# Farm_Pump.net
KiCad netlist of a schematic drawn in Altium Designer
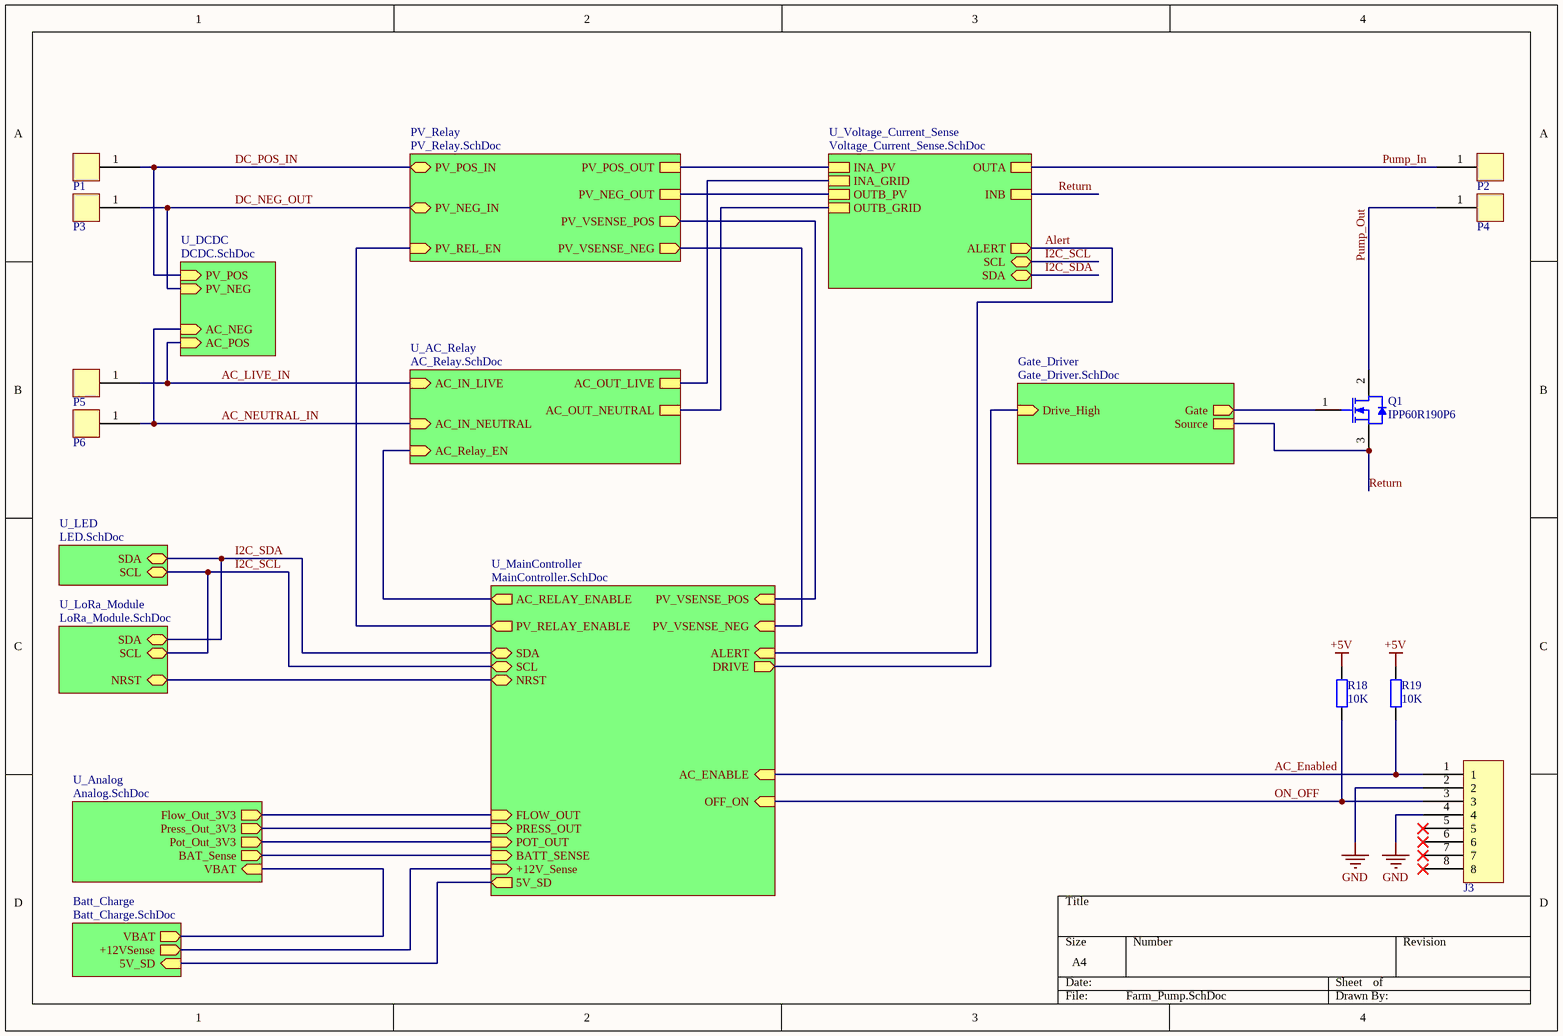
[diagram p0: Farm_Pump.SchDoc]

(export (version "E")
  (design (tool "Eeschema 10.0.6"))
  (components
    (comp (ref "J3")
      (value "MTJ-885X1")
      (footprint "MTJ-885X1")
      (fields (field (name "MANUFACTURER") "MODULAR JACK RJ45 8P8C"))
      (libsource (lib "Database_library") (part "MTJ-885X1"))
    )
    (comp (ref "P1")
      (value "1719189")
      (footprint "1719189")
      (fields (field (name "VOLTAGE") "1000") (field (name "MANUFACTURER") "Phoenix Contact"))
      (libsource (lib "Database_library") (part "1719189"))
    )
    (comp (ref "P2")
      (value "1719189")
      (footprint "1719189")
      (fields (field (name "VOLTAGE") "1000") (field (name "MANUFACTURER") "Phoenix Contact"))
      (libsource (lib "") (part "1719189_1"))
    )
    (comp (ref "P3")
      (value "1719189")
      (footprint "1719189")
      (fields (field (name "VOLTAGE") "1000") (field (name "MANUFACTURER") "Phoenix Contact"))
      (libsource (lib "Database_library") (part "1719189"))
    )
    (comp (ref "P4")
      (value "1719189")
      (footprint "1719189")
      (fields (field (name "VOLTAGE") "1000") (field (name "MANUFACTURER") "Phoenix Contact"))
      (libsource (lib "") (part "1719189_1"))
    )
    (comp (ref "P5")
      (value "1719189")
      (footprint "1719189")
      (fields (field (name "VOLTAGE") "1000") (field (name "MANUFACTURER") "Phoenix Contact"))
      (libsource (lib "Database_library") (part "1719189"))
    )
    (comp (ref "P6")
      (value "1719189")
      (footprint "1719189")
      (fields (field (name "VOLTAGE") "1000") (field (name "MANUFACTURER") "Phoenix Contact"))
      (libsource (lib "Database_library") (part "1719189"))
    )
    (comp (ref "Q1")
      (value "IPP60R190P6")
      (footprint "INF-PG-TO220-3-1_A_V")
      (description "N-Channel CoolMOS(TM) P6 Power Transistor, 600 V VDS, -55 to 150 degC, PG-TO220-3, Tube, Green")
      (fields (field (name "MANUFACTURER") "Infineon"))
      (libsource (lib "Altium Content Vault") (part "INF-NEMOS-GDS-3"))
    )
    (comp (ref "R18")
      (value "10K")
      (footprint "RES 0603/1608")
      (description "RES SMD 10K OHM 0.1% 1/10W 0603")
      (fields (field (name "PART NUMBER") "RG1608P-103-B-T5") (field (name "TOLERANCE") "0.1%"))
      (libsource (lib "electric_racing_lib") (part "Resistor"))
    )
    (comp (ref "R19")
      (value "10K")
      (footprint "RES 0603/1608")
      (description "RES SMD 10K OHM 0.1% 1/10W 0603")
      (fields (field (name "PART NUMBER") "RG1608P-103-B-T5") (field (name "TOLERANCE") "0.1%"))
      (libsource (lib "electric_racing_lib") (part "Resistor"))
    )
  )
  (nets
    (net (code "1") (name "+5V") (class "Default")
      (node (ref "R18") (pin "2") (pinfunction "2_2") (pintype "passive"))
      (node (ref "R19") (pin "2") (pinfunction "2_2") (pintype "passive"))
    )
    (net (code "4") (name "/AC_Enabled") (class "Default")
      (node (ref "J3") (pin "1") (pinfunction "1_1") (pintype "passive"))
      (node (ref "R19") (pin "1") (pinfunction "1_1") (pintype "passive"))
    )
    (net (code "5") (name "/AC_LIVE_IN") (class "Default")
      (node (ref "P5") (pin "1") (pinfunction "1_1") (pintype "passive"))
    )
    (net (code "6") (name "/AC_NEUTRAL_IN") (class "Default")
      (node (ref "P6") (pin "1") (pinfunction "1_1") (pintype "passive"))
    )
    (net (code "12") (name "/DC_NEG_OUT") (class "Default")
      (node (ref "P3") (pin "1") (pinfunction "1_1") (pintype "passive"))
    )
    (net (code "13") (name "/DC_POS_IN") (class "Default")
      (node (ref "P1") (pin "1") (pinfunction "1_1") (pintype "passive"))
    )
    (net (code "16") (name "/Gate") (class "Default")
      (node (ref "Q1") (pin "1") (pinfunction "GATE_1") (pintype "passive"))
    )
    (net (code "21") (name "/ON_OFF") (class "Default")
      (node (ref "J3") (pin "3") (pinfunction "3_3") (pintype "passive"))
      (node (ref "R18") (pin "1") (pinfunction "1_1") (pintype "passive"))
    )
    (net (code "28") (name "/Pump_In") (class "Default")
      (node (ref "P2") (pin "1") (pinfunction "1_1") (pintype "passive"))
    )
    (net (code "29") (name "/Pump_Out") (class "Default")
      (node (ref "P4") (pin "1") (pinfunction "1_1") (pintype "passive"))
      (node (ref "Q1") (pin "2") (pinfunction "DRAIN_2") (pintype "passive"))
    )
    (net (code "30") (name "/Return") (class "Default")
      (node (ref "Q1") (pin "3") (pinfunction "SOURCE_3") (pintype "passive"))
    )
    (net (code "32") (name "GND") (class "Default")
      (node (ref "J3") (pin "2") (pinfunction "2_2") (pintype "passive"))
      (node (ref "J3") (pin "4") (pinfunction "4_4") (pintype "passive"))
    )
    (net (code "33") (name "unconnected-(J3-Pad5)") (class "Default")
      (node (ref "J3") (pin "5") (pinfunction "5_5") (pintype "passive+no_connect"))
    )
    (net (code "34") (name "unconnected-(J3-Pad6)") (class "Default")
      (node (ref "J3") (pin "6") (pinfunction "6_6") (pintype "passive+no_connect"))
    )
    (net (code "35") (name "unconnected-(J3-Pad7)") (class "Default")
      (node (ref "J3") (pin "7") (pinfunction "7_7") (pintype "passive+no_connect"))
    )
    (net (code "36") (name "unconnected-(J3-Pad8)") (class "Default")
      (node (ref "J3") (pin "8") (pinfunction "8_8") (pintype "passive+no_connect"))
    )
  )
)
